# kegboard-coaster-alt.net
KiCad netlist of a schematic drawn in EAGLE
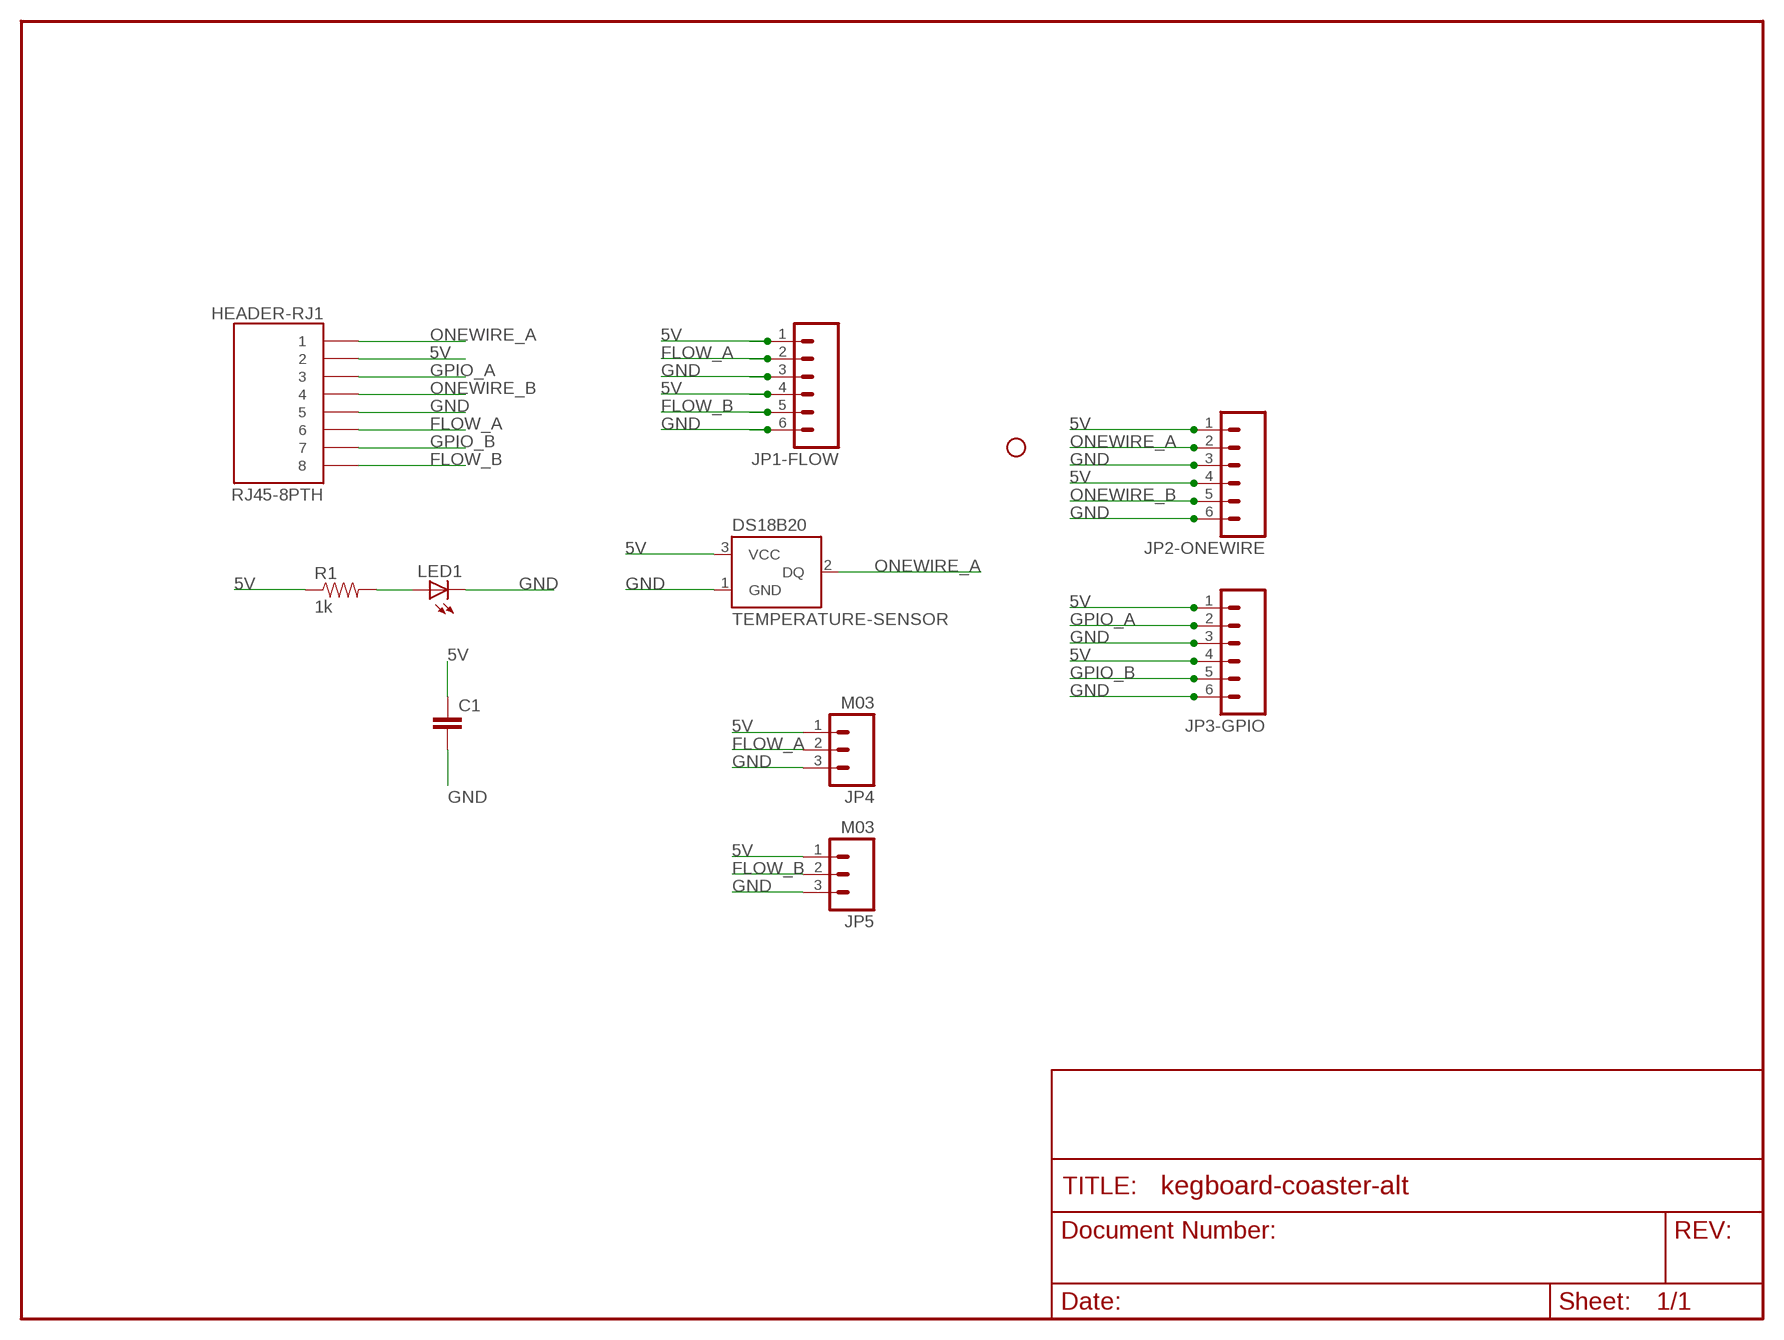
[diagram p0: schematic, sheet 1]

(export (version "E")
  (design (tool "Eeschema 10.0.6"))
  (components
    (comp (ref "C1")
      (value "CAPPTH2")
      (footprint "eagle-import:CAP-PTH-SMALL2")
      (libsource (lib "eagle-import") (part "CAPPTH2"))
    )
    (comp (ref "HEADER-RJ1")
      (value "RJ45-8PTH")
      (footprint "eagle-import:RJ45-8")
      (libsource (lib "eagle-import") (part "RJ45-8PTH"))
    )
    (comp (ref "JP1-FLOW")
      (value "M063.5MM-6")
      (footprint "eagle-import:SCREWTERMINAL-3.5MM-6")
      (libsource (lib "eagle-import") (part "M063.5MM-6"))
    )
    (comp (ref "JP2")
      (value "STAND-OFF")
      (footprint "eagle-import:STAND-OFF")
      (libsource (lib "eagle-import") (part "STAND-OFF"))
    )
    (comp (ref "JP2-ONEWIRE")
      (value "M063.5MM-6")
      (footprint "eagle-import:SCREWTERMINAL-3.5MM-6")
      (libsource (lib "eagle-import") (part "M063.5MM-6"))
    )
    (comp (ref "JP3-GPIO")
      (value "M063.5MM-6")
      (footprint "eagle-import:SCREWTERMINAL-3.5MM-6")
      (libsource (lib "eagle-import") (part "M063.5MM-6"))
    )
    (comp (ref "JP4")
      (value "M03")
      (footprint "eagle-import:53324-0360")
      (libsource (lib "eagle-import") (part "M03"))
    )
    (comp (ref "JP5")
      (value "M03")
      (footprint "eagle-import:53324-0360")
      (libsource (lib "eagle-import") (part "M03"))
    )
    (comp (ref "LED1")
      (value "LED3MM")
      (footprint "eagle-import:LED3MM")
      (libsource (lib "eagle-import") (part "LED3MM"))
    )
    (comp (ref "R1")
      (value "1k")
      (footprint "eagle-import:AXIAL-0.3")
      (libsource (lib "eagle-import") (part "RESISTORPTH1"))
    )
    (comp (ref "U$1")
      (value "TEMPERATURE-SENSOR")
      (footprint "eagle-import:TO-92")
      (libsource (lib "eagle-import") (part "TEMPERATURE-SENSOR"))
    )
  )
  (nets
    (net (code "1") (name "/5V") (class "Default")
      (node (ref "C1") (pin "1") (pinfunction "1_1") (pintype "passive"))
      (node (ref "HEADER-RJ1") (pin "2") (pinfunction "2_2") (pintype "bidirectional"))
      (node (ref "JP1-FLOW") (pin "1") (pinfunction "1_1") (pintype "passive"))
      (node (ref "JP1-FLOW") (pin "4") (pinfunction "4_4") (pintype "passive"))
      (node (ref "JP2-ONEWIRE") (pin "1") (pinfunction "1_1") (pintype "passive"))
      (node (ref "JP2-ONEWIRE") (pin "4") (pinfunction "4_4") (pintype "passive"))
      (node (ref "JP3-GPIO") (pin "1") (pinfunction "1_1") (pintype "passive"))
      (node (ref "JP3-GPIO") (pin "4") (pinfunction "4_4") (pintype "passive"))
      (node (ref "JP4") (pin "1") (pinfunction "1_1") (pintype "passive"))
      (node (ref "JP5") (pin "1") (pinfunction "1_1") (pintype "passive"))
      (node (ref "R1") (pin "P$1") (pinfunction "1_P$1") (pintype "passive"))
      (node (ref "U$1") (pin "3") (pinfunction "VCC_3") (pintype "bidirectional"))
    )
    (net (code "2") (name "/FLOW_A") (class "Default")
      (node (ref "HEADER-RJ1") (pin "6") (pinfunction "6_6") (pintype "bidirectional"))
      (node (ref "JP1-FLOW") (pin "2") (pinfunction "2_2") (pintype "passive"))
      (node (ref "JP4") (pin "2") (pinfunction "2_2") (pintype "passive"))
    )
    (net (code "3") (name "/FLOW_B") (class "Default")
      (node (ref "HEADER-RJ1") (pin "8") (pinfunction "8_8") (pintype "bidirectional"))
      (node (ref "JP1-FLOW") (pin "5") (pinfunction "5_5") (pintype "passive"))
      (node (ref "JP5") (pin "2") (pinfunction "2_2") (pintype "passive"))
    )
    (net (code "4") (name "/GND") (class "Default")
      (node (ref "C1") (pin "2") (pinfunction "2_2") (pintype "passive"))
      (node (ref "HEADER-RJ1") (pin "5") (pinfunction "5_5") (pintype "bidirectional"))
      (node (ref "JP1-FLOW") (pin "3") (pinfunction "3_3") (pintype "passive"))
      (node (ref "JP1-FLOW") (pin "6") (pinfunction "6_6") (pintype "passive"))
      (node (ref "JP2-ONEWIRE") (pin "3") (pinfunction "3_3") (pintype "passive"))
      (node (ref "JP2-ONEWIRE") (pin "6") (pinfunction "6_6") (pintype "passive"))
      (node (ref "JP3-GPIO") (pin "3") (pinfunction "3_3") (pintype "passive"))
      (node (ref "JP3-GPIO") (pin "6") (pinfunction "6_6") (pintype "passive"))
      (node (ref "JP4") (pin "3") (pinfunction "3_3") (pintype "passive"))
      (node (ref "JP5") (pin "3") (pinfunction "3_3") (pintype "passive"))
      (node (ref "LED1") (pin "K") (pinfunction "C_K") (pintype "passive"))
      (node (ref "U$1") (pin "1") (pinfunction "GND_1") (pintype "bidirectional"))
    )
    (net (code "5") (name "/GPIO_A") (class "Default")
      (node (ref "HEADER-RJ1") (pin "3") (pinfunction "3_3") (pintype "bidirectional"))
      (node (ref "JP3-GPIO") (pin "2") (pinfunction "2_2") (pintype "passive"))
    )
    (net (code "6") (name "/GPIO_B") (class "Default")
      (node (ref "HEADER-RJ1") (pin "7") (pinfunction "7_7") (pintype "bidirectional"))
      (node (ref "JP3-GPIO") (pin "5") (pinfunction "5_5") (pintype "passive"))
    )
    (net (code "7") (name "/ONEWIRE_A") (class "Default")
      (node (ref "HEADER-RJ1") (pin "1") (pinfunction "1_1") (pintype "bidirectional"))
      (node (ref "JP2-ONEWIRE") (pin "2") (pinfunction "2_2") (pintype "passive"))
      (node (ref "U$1") (pin "2") (pinfunction "DQ_2") (pintype "bidirectional"))
    )
    (net (code "8") (name "/ONEWIRE_B") (class "Default")
      (node (ref "HEADER-RJ1") (pin "4") (pinfunction "4_4") (pintype "bidirectional"))
      (node (ref "JP2-ONEWIRE") (pin "5") (pinfunction "5_5") (pintype "passive"))
    )
    (net (code "9") (name "Net-(R1-2)") (class "Default")
      (node (ref "LED1") (pin "A") (pinfunction "A_A") (pintype "passive"))
      (node (ref "R1") (pin "P$2") (pinfunction "2_P$2") (pintype "passive"))
    )
  )
)
